# pca63550.net
KiCad netlist of a schematic drawn in Altium Designer
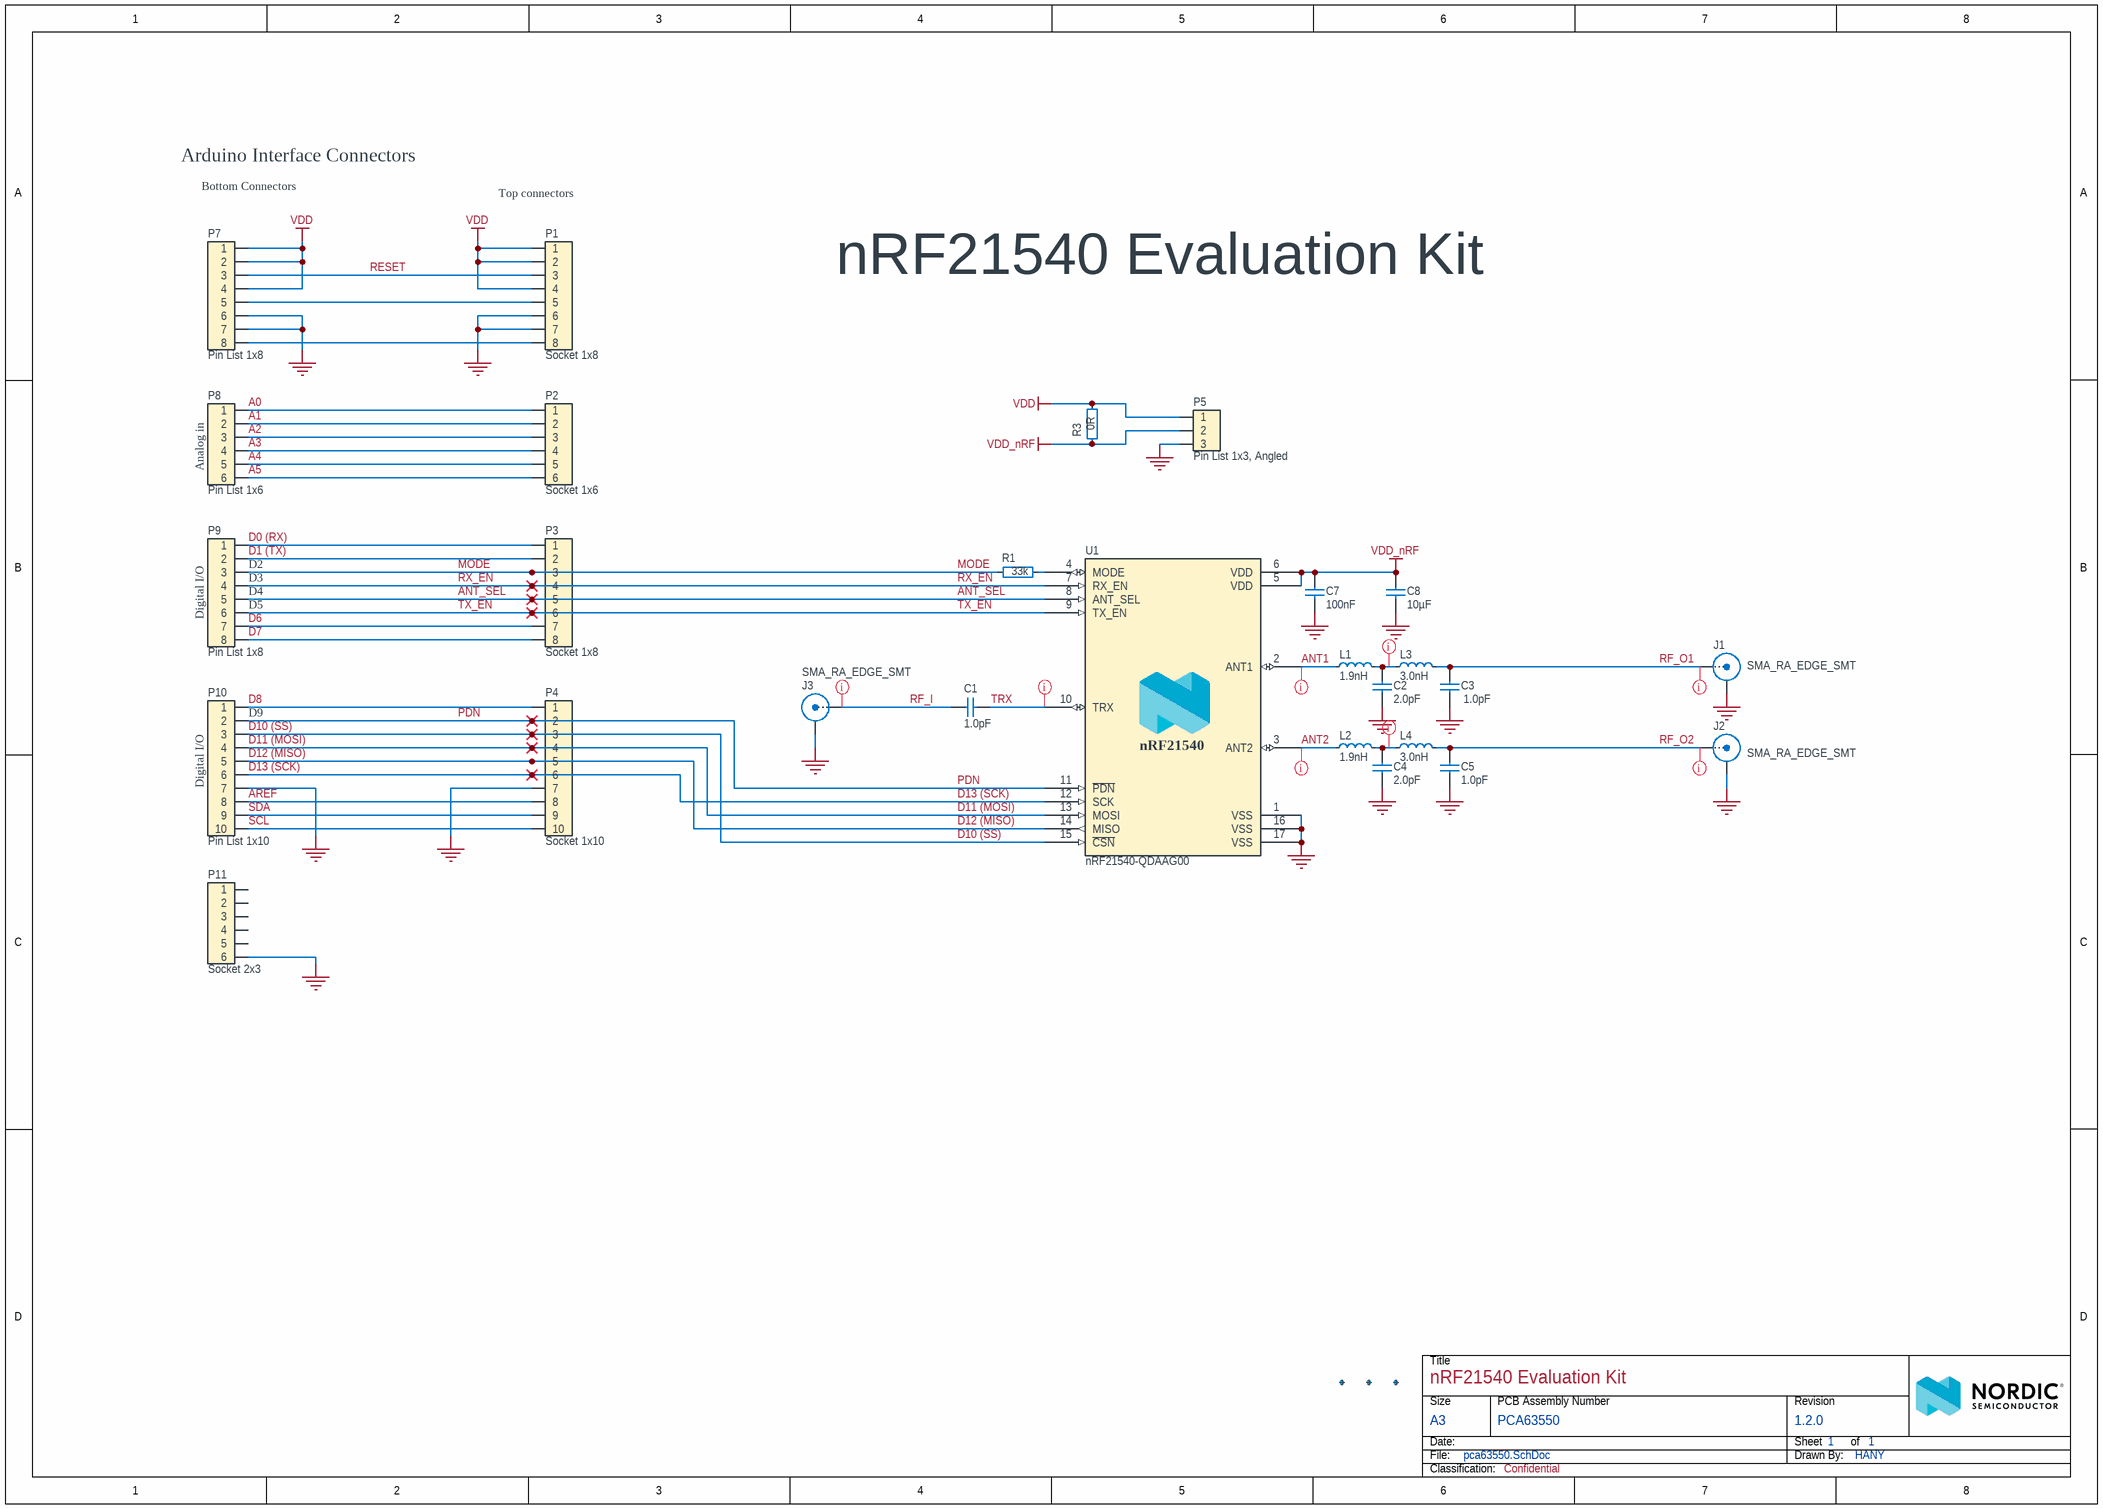
[diagram p0: pca63550.SchDoc]

(export (version "E")
  (design (tool "Eeschema 10.0.6"))
  (components
    (comp (ref "C1")
      (value "1.0pF")
      (footprint "CAPC0603X03L_C")
      (description "Capacitor, C0G, ±0.1pF, 25V")
      (fields
        (field (name "PART NUMBER") "C0201-1p0")
        (field (name "MANUFACTURER") "Murata")
        (field (name "AUTHOR") "rsk")
      )
      (libsource (lib "AltiumLib") (part "CAP"))
    )
    (comp (ref "C2")
      (value "2.0pF")
      (footprint "CAPC0603X03L_C")
      (description "Capacitor, NP0, ±0.05pF, 25V")
      (fields
        (field (name "PART NUMBER") "C0201-2.0p-HQ-Murata")
        (field (name "MANUFACTURER") "Murata")
        (field (name "AUTHOR") "rsk")
      )
      (libsource (lib "AltiumLib") (part "CAP"))
    )
    (comp (ref "C3")
      (value "1.0pF")
      (footprint "CAPC0603X03L_C")
      (description "RF Chip Cap 0201")
      (fields
        (field (name "PART NUMBER") "C0201-1.0p_RF")
        (field (name "MANUFACTURER") "N.A.")
        (field (name "AUTHOR") "rsk")
      )
      (libsource (lib "AltiumLib") (part "CAP"))
    )
    (comp (ref "C4")
      (value "2.0pF")
      (footprint "CAPC0603X03L_C")
      (description "Capacitor, NP0, ±0.05pF, 25V")
      (fields
        (field (name "PART NUMBER") "C0201-2.0p-HQ-Murata")
        (field (name "MANUFACTURER") "Murata")
        (field (name "AUTHOR") "rsk")
      )
      (libsource (lib "AltiumLib") (part "CAP"))
    )
    (comp (ref "C5")
      (value "1.0pF")
      (footprint "CAPC0603X03L_C")
      (description "RF Chip Cap 0201")
      (fields
        (field (name "PART NUMBER") "C0201-1.0p_RF")
        (field (name "MANUFACTURER") "N.A.")
        (field (name "AUTHOR") "rsk")
      )
      (libsource (lib "AltiumLib") (part "CAP"))
    )
    (comp (ref "C7")
      (value "100nF")
      (footprint "CAPC0603X03L_C")
      (description "Capacitor, X5R, ±10%")
      (fields
        (field (name "PART NUMBER") "C0201-100n")
        (field (name "MANUFACTURER") "N.A.")
        (field (name "AUTHOR") "rsk")
      )
      (libsource (lib "AltiumLib") (part "CAP"))
    )
    (comp (ref "C8")
      (value "10µF")
      (footprint "CAPC1608X06L")
      (description "Capacitor, X5R, ±20%")
      (fields
        (field (name "PART NUMBER") "C0603-10µ")
        (field (name "MANUFACTURER") "N.A.")
        (field (name "AUTHOR") "rsk")
      )
      (libsource (lib "AltiumLib") (part "CAP"))
    )
    (comp (ref "Fid1")
      (value "Fiducial mark")
      (footprint "Fiducial")
      (description "Fiducial Mark")
      (fields
        (field (name "PART NUMBER") "Fid-Mark")
        (field (name "MANUFACTURER") "N.A.")
        (field (name "AUTHOR") "rsk")
      )
      (libsource (lib "AltiumLib") (part "Fiducial"))
    )
    (comp (ref "Fid2")
      (value "Fiducial mark")
      (footprint "Fiducial")
      (description "Fiducial Mark")
      (fields
        (field (name "PART NUMBER") "Fid-Mark")
        (field (name "MANUFACTURER") "N.A.")
        (field (name "AUTHOR") "rsk")
      )
      (libsource (lib "AltiumLib") (part "Fiducial"))
    )
    (comp (ref "Fid3")
      (value "Fiducial mark")
      (footprint "Fiducial")
      (description "Fiducial Mark")
      (fields
        (field (name "PART NUMBER") "Fid-Mark")
        (field (name "MANUFACTURER") "N.A.")
        (field (name "AUTHOR") "rsk")
      )
      (libsource (lib "AltiumLib") (part "Fiducial"))
    )
    (comp (ref "J1")
      (value "SMA_2081005-1")
      (footprint "SMA_2081005-1")
      (description "SMA, Female, Right Angle, TH/SMT, 50Ohm, Board Edge")
      (fields
        (field (name "PART NUMBER") "SMA_RA_EDGE_SMT")
        (field (name "MANUFACTURER") "CompuPack")
        (field (name "MANUFACTURER PART NUMBER") "ARFRBE22029-GGP")
        (field (name "AUTHOR") "rsk")
      )
      (libsource (lib "AltiumLib") (part "SMA"))
    )
    (comp (ref "J2")
      (value "SMA_2081005-1")
      (footprint "SMA_2081005-1")
      (description "SMA, Female, Right Angle, TH/SMT, 50Ohm, Board Edge")
      (fields
        (field (name "PART NUMBER") "SMA_RA_EDGE_SMT")
        (field (name "MANUFACTURER") "CompuPack")
        (field (name "MANUFACTURER PART NUMBER") "ARFRBE22029-GGP")
        (field (name "AUTHOR") "rsk")
      )
      (libsource (lib "AltiumLib") (part "SMA"))
    )
    (comp (ref "J3")
      (value "SMA_2081005-1")
      (footprint "SMA_2081005-1")
      (description "SMA, Female, Right Angle, TH/SMT, 50Ohm, Board Edge")
      (fields
        (field (name "PART NUMBER") "SMA_RA_EDGE_SMT")
        (field (name "MANUFACTURER") "CompuPack")
        (field (name "MANUFACTURER PART NUMBER") "ARFRBE22029-GGP")
        (field (name "AUTHOR") "rsk")
      )
      (libsource (lib "AltiumLib") (part "SMA"))
    )
    (comp (ref "L1")
      (value "1.9nH")
      (footprint "INDC0603X03L_C")
      (description "Inductor, 600mA, ±0.1ｎH, 120mOhm")
      (fields
        (field (name "PART NUMBER") "L0201-1n9-HQ-Murata")
        (field (name "MANUFACTURER") "Murata")
        (field (name "AUTHOR") "rsk")
      )
      (libsource (lib "AltiumLib") (part "IND"))
    )
    (comp (ref "L2")
      (value "1.9nH")
      (footprint "INDC0603X03L_C")
      (description "Inductor, 600mA, ±0.1ｎH, 120mOhm")
      (fields
        (field (name "PART NUMBER") "L0201-1n9-HQ-Murata")
        (field (name "MANUFACTURER") "Murata")
        (field (name "AUTHOR") "rsk")
      )
      (libsource (lib "AltiumLib") (part "IND"))
    )
    (comp (ref "L3")
      (value "3.0nH")
      (footprint "INDC0603X03L_C")
      (description "Inductor, 600mA, ±0.1ｎH, 120mOhm")
      (fields
        (field (name "PART NUMBER") "L0201-3n0-HQ-Murata")
        (field (name "MANUFACTURER") "Murata")
        (field (name "AUTHOR") "rsk")
      )
      (libsource (lib "AltiumLib") (part "IND"))
    )
    (comp (ref "L4")
      (value "3.0nH")
      (footprint "INDC0603X03L_C")
      (description "Inductor, 600mA, ±0.1ｎH, 120mOhm")
      (fields
        (field (name "PART NUMBER") "L0201-3n0-HQ-Murata")
        (field (name "MANUFACTURER") "Murata")
        (field (name "AUTHOR") "rsk")
      )
      (libsource (lib "AltiumLib") (part "IND"))
    )
    (comp (ref "P1")
      (value "Socket 1x8")
      (footprint "SOCKET_1x8_SMD")
      (description "Socket 1x8, 2.54mm (100mil), SMD")
      (fields
        (field (name "PART NUMBER") "Socket 1x8 SMD")
        (field (name "MANUFACTURER") "W-CON")
        (field (name "AUTHOR") "rsk")
      )
      (libsource (lib "") (part "CONN-8_1"))
    )
    (comp (ref "P2")
      (value "Socket 1x6")
      (footprint "SOCKET_1x6_SMD")
      (description "Socket 1x6, 2.54mm (100mil), SMD")
      (fields
        (field (name "PART NUMBER") "Socket 1x6 SMD")
        (field (name "MANUFACTURER") "W-CON")
        (field (name "AUTHOR") "rsk")
      )
      (libsource (lib "AltiumLib") (part "CONN-6"))
    )
    (comp (ref "P3")
      (value "Socket 1x8")
      (footprint "SOCKET_1x8_SMD")
      (description "Socket 1x8, 2.54mm (100mil), SMD")
      (fields
        (field (name "PART NUMBER") "Socket 1x8 SMD")
        (field (name "MANUFACTURER") "W-CON")
        (field (name "AUTHOR") "rsk")
      )
      (libsource (lib "") (part "CONN-8_1"))
    )
    (comp (ref "P4")
      (value "Socket 1x10")
      (footprint "SOCKET_1x10_SMD")
      (description "Socket 1x10, 2.54mm (100mil), SMD")
      (fields
        (field (name "PART NUMBER") "Socket 1x10 SMD")
        (field (name "MANUFACTURER") "W-CON")
        (field (name "AUTHOR") "rsk")
      )
      (libsource (lib "AltiumLib") (part "CONN-10"))
    )
    (comp (ref "P5")
      (value "Pin List 1x3, Angled")
      (footprint "LIST_ANG_1x3-SMD-2.54MM")
      (description "Pin List 1x3, 2.54mm (100mil), Right Angled, SMD")
      (fields
        (field (name "PART NUMBER") "Pin List Ang 1x3 SMD, 2.54mm")
        (field (name "MANUFACTURER") "W-CON")
        (field (name "AUTHOR") "rsk")
      )
      (libsource (lib "AltiumLib") (part "CONN-3"))
    )
    (comp (ref "P7")
      (value "Pin List 1x8")
      (footprint "LIST_1x8_SMD")
      (description "Pin List 1x8, 2.54mm (100mil), SMD")
      (fields
        (field (name "PART NUMBER") "Pin List 1x8 SMD")
        (field (name "MANUFACTURER") "W-CON")
        (field (name "AUTHOR") "rsk")
      )
      (libsource (lib "AltiumLib") (part "CONN-8"))
    )
    (comp (ref "P8")
      (value "Pin List 1x6")
      (footprint "LIST_1x6_SMD")
      (description "Pin List 1x6, 2.54mm (100mil), SMD")
      (fields
        (field (name "PART NUMBER") "Pin List 1x6 SMD")
        (field (name "MANUFACTURER") "W-CON")
        (field (name "AUTHOR") "rsk")
      )
      (libsource (lib "") (part "CONN-6_1"))
    )
    (comp (ref "P9")
      (value "Pin List 1x8")
      (footprint "LIST_1x8_SMD")
      (description "Pin List 1x8, 2.54mm (100mil), SMD")
      (fields
        (field (name "PART NUMBER") "Pin List 1x8 SMD")
        (field (name "MANUFACTURER") "W-CON")
        (field (name "AUTHOR") "rsk")
      )
      (libsource (lib "AltiumLib") (part "CONN-8"))
    )
    (comp (ref "P10")
      (value "Pin List 1x10")
      (footprint "LIST_1x10_SMD")
      (description "Pin List 1x10, 2.54mm (100mil), SMD")
      (fields
        (field (name "PART NUMBER") "Pin List 1x10 SMD")
        (field (name "MANUFACTURER") "W-CON")
        (field (name "AUTHOR") "rsk")
      )
      (libsource (lib "") (part "CONN-10_1"))
    )
    (comp (ref "P11")
      (value "Socket 2x3")
      (footprint "SOCKET_2x3_SMD-2.54mm-bottom")
      (description "Socket 2x3, 2.54mm (100mil), SMD")
      (fields
        (field (name "PART NUMBER") "Socket 2x3 SMD Bottom")
        (field (name "MANUFACTURER") "W-CON")
        (field (name "AUTHOR") "rsk")
      )
      (libsource (lib "") (part "CONN-6_1"))
    )
    (comp (ref "R1")
      (value "33k")
      (footprint "RESC0603X03L_C")
      (description "Resistor, ±1%, 0.05W")
      (fields
        (field (name "PART NUMBER") "R0201-33k")
        (field (name "MANUFACTURER") "N.A.")
        (field (name "AUTHOR") "rsk")
      )
      (libsource (lib "AltiumLib") (part "RES"))
    )
    (comp (ref "R3")
      (value "0R")
      (footprint "RESC1005X04L")
      (description "Resistor, ±5%, 0.063W")
      (fields
        (field (name "PART NUMBER") "R0402-0R")
        (field (name "MANUFACTURER") "N.A.")
        (field (name "AUTHOR") "rsk")
      )
      (libsource (lib "AltiumLib") (part "RES"))
    )
    (comp (ref "U1")
      (value "nRF21540-QDAAG00")
      (footprint "QFN65P400X400X65_HS-17N")
      (description "Radio front-end / range extender for 2.4GHz")
      (fields
        (field (name "PART NUMBER") "nRF21540-QDAAG0")
        (field (name "MANUFACTURER") "Nordic Semiconductor")
        (field (name "AUTHOR") "hany")
      )
      (libsource (lib "AltiumLib") (part "nRF21540-QDAA"))
    )
  )
  (nets
    (net (code "1") (name "/A0") (class "Default")
      (node (ref "P2") (pin "1") (pinfunction "1_1") (pintype "passive"))
      (node (ref "P8") (pin "1") (pinfunction "1_1") (pintype "passive"))
    )
    (net (code "2") (name "/A1") (class "Default")
      (node (ref "P2") (pin "2") (pinfunction "2_2") (pintype "passive"))
      (node (ref "P8") (pin "2") (pinfunction "2_2") (pintype "passive"))
    )
    (net (code "3") (name "/A2") (class "Default")
      (node (ref "P2") (pin "3") (pinfunction "3_3") (pintype "passive"))
      (node (ref "P8") (pin "3") (pinfunction "3_3") (pintype "passive"))
    )
    (net (code "4") (name "/A3") (class "Default")
      (node (ref "P2") (pin "4") (pinfunction "4_4") (pintype "passive"))
      (node (ref "P8") (pin "4") (pinfunction "4_4") (pintype "passive"))
    )
    (net (code "5") (name "/A4") (class "Default")
      (node (ref "P2") (pin "5") (pinfunction "5_5") (pintype "passive"))
      (node (ref "P8") (pin "5") (pinfunction "5_5") (pintype "passive"))
    )
    (net (code "6") (name "/A5") (class "Default")
      (node (ref "P2") (pin "6") (pinfunction "6_6") (pintype "passive"))
      (node (ref "P8") (pin "6") (pinfunction "6_6") (pintype "passive"))
    )
    (net (code "7") (name "/ANT1") (class "Default")
      (node (ref "L1") (pin "1") (pinfunction "1_1") (pintype "passive"))
      (node (ref "U1") (pin "2") (pinfunction "ANT1_2") (pintype "bidirectional"))
    )
    (net (code "8") (name "/ANT2") (class "Default")
      (node (ref "L2") (pin "1") (pinfunction "1_1") (pintype "passive"))
      (node (ref "U1") (pin "3") (pinfunction "ANT2_3") (pintype "bidirectional"))
    )
    (net (code "9") (name "/ANT_SEL") (class "Default")
      (node (ref "P3") (pin "5") (pinfunction "5_5") (pintype "passive"))
      (node (ref "P9") (pin "5") (pinfunction "5_5") (pintype "passive"))
      (node (ref "U1") (pin "8") (pinfunction "ANT_SEL_8") (pintype "input"))
    )
    (net (code "10") (name "/AREF") (class "Default")
      (node (ref "P10") (pin "8") (pinfunction "8_8") (pintype "passive"))
      (node (ref "P4") (pin "8") (pinfunction "8_8") (pintype "passive"))
    )
    (net (code "11") (name "/D0 (RX)") (class "Default")
      (node (ref "P3") (pin "1") (pinfunction "1_1") (pintype "passive"))
      (node (ref "P9") (pin "1") (pinfunction "1_1") (pintype "passive"))
    )
    (net (code "12") (name "/D1 (TX)") (class "Default")
      (node (ref "P3") (pin "2") (pinfunction "2_2") (pintype "passive"))
      (node (ref "P9") (pin "2") (pinfunction "2_2") (pintype "passive"))
    )
    (net (code "13") (name "/D6") (class "Default")
      (node (ref "P3") (pin "7") (pinfunction "7_7") (pintype "passive"))
      (node (ref "P9") (pin "7") (pinfunction "7_7") (pintype "passive"))
    )
    (net (code "14") (name "/D7") (class "Default")
      (node (ref "P3") (pin "8") (pinfunction "8_8") (pintype "passive"))
      (node (ref "P9") (pin "8") (pinfunction "8_8") (pintype "passive"))
    )
    (net (code "15") (name "/D8") (class "Default")
      (node (ref "P10") (pin "1") (pinfunction "1_1") (pintype "passive"))
      (node (ref "P4") (pin "1") (pinfunction "1_1") (pintype "passive"))
    )
    (net (code "16") (name "/D10 (SS)") (class "Default")
      (node (ref "P10") (pin "3") (pinfunction "3_3") (pintype "passive"))
      (node (ref "P4") (pin "3") (pinfunction "3_3") (pintype "passive"))
      (node (ref "U1") (pin "15") (pinfunction "~{CSN}_15") (pintype "input"))
    )
    (net (code "17") (name "/D11 (MOSI)") (class "Default")
      (node (ref "P10") (pin "4") (pinfunction "4_4") (pintype "passive"))
      (node (ref "P4") (pin "4") (pinfunction "4_4") (pintype "passive"))
      (node (ref "U1") (pin "13") (pinfunction "MOSI_13") (pintype "input"))
    )
    (net (code "18") (name "/D12 (MISO)") (class "Default")
      (node (ref "P10") (pin "5") (pinfunction "5_5") (pintype "passive"))
      (node (ref "P4") (pin "5") (pinfunction "5_5") (pintype "passive"))
      (node (ref "U1") (pin "14") (pinfunction "MISO_14") (pintype "output"))
    )
    (net (code "19") (name "/D13 (SCK)") (class "Default")
      (node (ref "P10") (pin "6") (pinfunction "6_6") (pintype "passive"))
      (node (ref "P4") (pin "6") (pinfunction "6_6") (pintype "passive"))
      (node (ref "U1") (pin "12") (pinfunction "SCK_12") (pintype "input"))
    )
    (net (code "20") (name "/MODE") (class "Default")
      (node (ref "P3") (pin "3") (pinfunction "3_3") (pintype "passive"))
      (node (ref "P9") (pin "3") (pinfunction "3_3") (pintype "passive"))
      (node (ref "R1") (pin "2") (pinfunction "2_2") (pintype "passive"))
    )
    (net (code "21") (name "/PDN") (class "Default")
      (node (ref "P10") (pin "2") (pinfunction "2_2") (pintype "passive"))
      (node (ref "P4") (pin "2") (pinfunction "2_2") (pintype "passive"))
      (node (ref "U1") (pin "11") (pinfunction "~{PDN}_11") (pintype "input"))
    )
    (net (code "22") (name "/RESET") (class "Default")
      (node (ref "P1") (pin "3") (pinfunction "3_3") (pintype "passive"))
      (node (ref "P7") (pin "3") (pinfunction "3_3") (pintype "passive"))
    )
    (net (code "23") (name "/RF_I") (class "Default")
      (node (ref "C1") (pin "1") (pinfunction "1_1") (pintype "passive"))
      (node (ref "J3") (pin "1") (pinfunction "X_1") (pintype "passive"))
    )
    (net (code "24") (name "/RF_O1") (class "Default")
      (node (ref "C3") (pin "2") (pinfunction "2_2") (pintype "passive"))
      (node (ref "J1") (pin "1") (pinfunction "X_1") (pintype "passive"))
      (node (ref "L3") (pin "2") (pinfunction "2_2") (pintype "passive"))
    )
    (net (code "25") (name "/RF_O2") (class "Default")
      (node (ref "C5") (pin "2") (pinfunction "2_2") (pintype "passive"))
      (node (ref "J2") (pin "1") (pinfunction "X_1") (pintype "passive"))
      (node (ref "L4") (pin "2") (pinfunction "2_2") (pintype "passive"))
    )
    (net (code "26") (name "/RX_EN") (class "Default")
      (node (ref "P3") (pin "4") (pinfunction "4_4") (pintype "passive"))
      (node (ref "P9") (pin "4") (pinfunction "4_4") (pintype "passive"))
      (node (ref "U1") (pin "7") (pinfunction "RX_EN_7") (pintype "input"))
    )
    (net (code "27") (name "/SCL") (class "Default")
      (node (ref "P10") (pin "10") (pinfunction "10_10") (pintype "passive"))
      (node (ref "P4") (pin "10") (pinfunction "10_10") (pintype "passive"))
    )
    (net (code "28") (name "/SDA") (class "Default")
      (node (ref "P10") (pin "9") (pinfunction "9_9") (pintype "passive"))
      (node (ref "P4") (pin "9") (pinfunction "9_9") (pintype "passive"))
    )
    (net (code "29") (name "/TRX") (class "Default")
      (node (ref "C1") (pin "2") (pinfunction "2_2") (pintype "passive"))
      (node (ref "U1") (pin "10") (pinfunction "TRX_10") (pintype "bidirectional"))
    )
    (net (code "30") (name "/TX_EN") (class "Default")
      (node (ref "P3") (pin "6") (pinfunction "6_6") (pintype "passive"))
      (node (ref "P9") (pin "6") (pinfunction "6_6") (pintype "passive"))
      (node (ref "U1") (pin "9") (pinfunction "TX_EN_9") (pintype "input"))
    )
    (net (code "31") (name "GND") (class "Default")
      (node (ref "C2") (pin "1") (pinfunction "1_1") (pintype "passive"))
      (node (ref "C3") (pin "1") (pinfunction "1_1") (pintype "passive"))
      (node (ref "C4") (pin "1") (pinfunction "1_1") (pintype "passive"))
      (node (ref "C5") (pin "1") (pinfunction "1_1") (pintype "passive"))
      (node (ref "C7") (pin "1") (pinfunction "1_1") (pintype "passive"))
      (node (ref "C8") (pin "1") (pinfunction "1_1") (pintype "passive"))
      (node (ref "J1") (pin "2") (pinfunction "Y_2") (pintype "passive"))
      (node (ref "J2") (pin "2") (pinfunction "Y_2") (pintype "passive"))
      (node (ref "J3") (pin "2") (pinfunction "Y_2") (pintype "passive"))
      (node (ref "P1") (pin "6") (pinfunction "6_6") (pintype "passive"))
      (node (ref "P1") (pin "7") (pinfunction "7_7") (pintype "passive"))
      (node (ref "P10") (pin "7") (pinfunction "7_7") (pintype "passive"))
      (node (ref "P11") (pin "6") (pinfunction "6_6") (pintype "passive"))
      (node (ref "P4") (pin "7") (pinfunction "7_7") (pintype "passive"))
      (node (ref "P5") (pin "3") (pinfunction "3_3") (pintype "passive"))
      (node (ref "P7") (pin "6") (pinfunction "6_6") (pintype "passive"))
      (node (ref "P7") (pin "7") (pinfunction "7_7") (pintype "passive"))
      (node (ref "U1") (pin "1") (pinfunction "VSS_1") (pintype "power_in"))
      (node (ref "U1") (pin "16") (pinfunction "VSS_16") (pintype "power_in"))
      (node (ref "U1") (pin "17") (pinfunction "VSS_17") (pintype "power_in"))
    )
    (net (code "32") (name "Net-(C2-Pad2)") (class "Default")
      (node (ref "C2") (pin "2") (pinfunction "2_2") (pintype "passive"))
      (node (ref "L1") (pin "2") (pinfunction "2_2") (pintype "passive"))
      (node (ref "L3") (pin "1") (pinfunction "1_1") (pintype "passive"))
    )
    (net (code "33") (name "Net-(C4-Pad2)") (class "Default")
      (node (ref "C4") (pin "2") (pinfunction "2_2") (pintype "passive"))
      (node (ref "L2") (pin "2") (pinfunction "2_2") (pintype "passive"))
      (node (ref "L4") (pin "1") (pinfunction "1_1") (pintype "passive"))
    )
    (net (code "34") (name "Net-(P1-Pad5)") (class "Default")
      (node (ref "P1") (pin "5") (pinfunction "5_5") (pintype "passive"))
      (node (ref "P7") (pin "5") (pinfunction "5_5") (pintype "passive"))
    )
    (net (code "35") (name "Net-(P1-Pad8)") (class "Default")
      (node (ref "P1") (pin "8") (pinfunction "8_8") (pintype "passive"))
      (node (ref "P7") (pin "8") (pinfunction "8_8") (pintype "passive"))
    )
    (net (code "36") (name "Net-(U1-MODE)") (class "Default")
      (node (ref "R1") (pin "1") (pinfunction "1_1") (pintype "passive"))
      (node (ref "U1") (pin "4") (pinfunction "MODE_4") (pintype "bidirectional"))
    )
    (net (code "37") (name "VDD") (class "Default")
      (node (ref "P1") (pin "1") (pinfunction "1_1") (pintype "passive"))
      (node (ref "P1") (pin "2") (pinfunction "2_2") (pintype "passive"))
      (node (ref "P1") (pin "4") (pinfunction "4_4") (pintype "passive"))
      (node (ref "P5") (pin "1") (pinfunction "1_1") (pintype "passive"))
      (node (ref "P7") (pin "1") (pinfunction "1_1") (pintype "passive"))
      (node (ref "P7") (pin "2") (pinfunction "2_2") (pintype "passive"))
      (node (ref "P7") (pin "4") (pinfunction "4_4") (pintype "passive"))
      (node (ref "R3") (pin "2") (pinfunction "2_2") (pintype "passive"))
    )
    (net (code "38") (name "VDD_nRF") (class "Default")
      (node (ref "C7") (pin "2") (pinfunction "2_2") (pintype "passive"))
      (node (ref "C8") (pin "2") (pinfunction "2_2") (pintype "passive"))
      (node (ref "P5") (pin "2") (pinfunction "2_2") (pintype "passive"))
      (node (ref "R3") (pin "1") (pinfunction "1_1") (pintype "passive"))
      (node (ref "U1") (pin "5") (pinfunction "VDD_5") (pintype "power_in"))
      (node (ref "U1") (pin "6") (pinfunction "VDD_6") (pintype "power_in"))
    )
    (net (code "39") (name "unconnected-(P11-Pad1)") (class "Default")
      (node (ref "P11") (pin "1") (pinfunction "1_1") (pintype "passive"))
    )
    (net (code "40") (name "unconnected-(P11-Pad2)") (class "Default")
      (node (ref "P11") (pin "2") (pinfunction "2_2") (pintype "passive"))
    )
    (net (code "41") (name "unconnected-(P11-Pad3)") (class "Default")
      (node (ref "P11") (pin "3") (pinfunction "3_3") (pintype "passive"))
    )
    (net (code "42") (name "unconnected-(P11-Pad4)") (class "Default")
      (node (ref "P11") (pin "4") (pinfunction "4_4") (pintype "passive"))
    )
    (net (code "43") (name "unconnected-(P11-Pad5)") (class "Default")
      (node (ref "P11") (pin "5") (pinfunction "5_5") (pintype "passive"))
    )
  )
)
